# Sheet1.net
KiCad netlist of a schematic drawn in Altium Designer
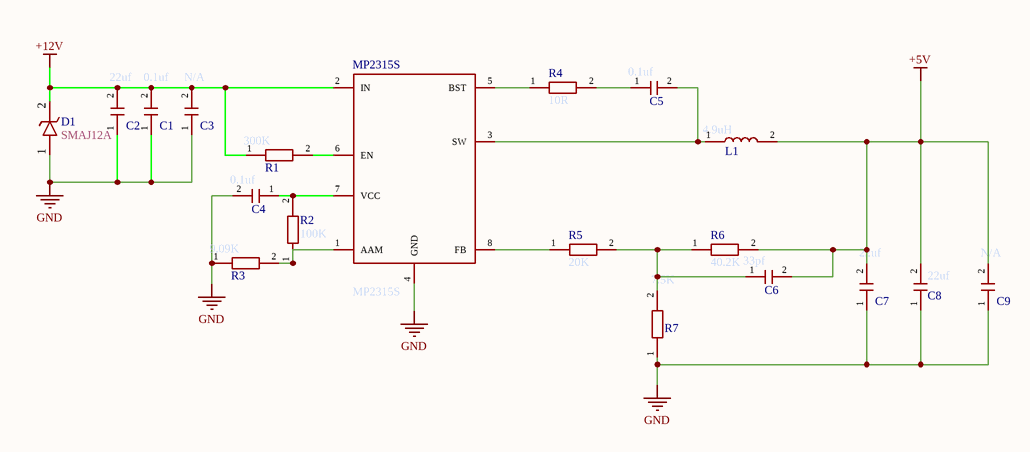
[diagram p0: Sheet1.SchDoc]

(export (version "E")
  (design (tool "Eeschema 10.0.6"))
  (components
    (comp (ref "C1") (value "0.1uf") (footprint "0603C") (libsource (lib "Schlib1") (part "capacitor")))
    (comp (ref "C2") (value "22uf") (footprint "1206C") (libsource (lib "Schlib1") (part "capacitor")))
    (comp (ref "C3") (value "N/A") (footprint "1206C") (libsource (lib "Schlib1") (part "capacitor")))
    (comp (ref "C4")
      (value "0.1uf")
      (footprint "www.zbpcb.com-JL_PCB:0603C")
      (libsource (lib "Schlib1") (part "capacitor"))
    )
    (comp (ref "C5")
      (value "0.1uf")
      (footprint "www.zbpcb.com-JL_PCB:0603C")
      (libsource (lib "Schlib1") (part "capacitor"))
    )
    (comp (ref "C6") (value "33pf") (footprint "0603C") (libsource (lib "Schlib1") (part "capacitor")))
    (comp (ref "C7") (value "22uf") (footprint "0805c") (libsource (lib "Schlib1") (part "capacitor")))
    (comp (ref "C8") (value "22uf") (footprint "0805c") (libsource (lib "Schlib1") (part "capacitor")))
    (comp (ref "C9") (value "N/A") (footprint "0805c") (libsource (lib "Schlib1") (part "capacitor")))
    (comp (ref "D1") (value "SMAJ12A") (footprint "SMA") (libsource (lib "Schlib1") (part "D")))
    (comp (ref "L1") (value "4.9uH") (footprint "L_pcb") (libsource (lib "Schlib1") (part "inductance")))
    (comp (ref "MP2315S")
      (value "MP2315S")
      (footprint "MP2315_PCB")
      (libsource (lib "Schlib1") (part "MP2315S"))
    )
    (comp (ref "R1") (value "300K") (footprint "0603R") (libsource (lib "Schlib1") (part "resistance")))
    (comp (ref "R2") (value "100K") (footprint "0603R") (libsource (lib "Schlib1") (part "resistance")))
    (comp (ref "R3") (value "9.09K") (footprint "0603R") (libsource (lib "Schlib1") (part "resistance")))
    (comp (ref "R4") (value "10R") (footprint "0603R") (libsource (lib "Schlib1") (part "resistance")))
    (comp (ref "R5") (value "20K") (footprint "0603R") (libsource (lib "Schlib1") (part "resistance")))
    (comp (ref "R6") (value "40.2K") (footprint "0603R") (libsource (lib "Schlib1") (part "resistance")))
    (comp (ref "R7") (value "7.5K") (footprint "0603R") (libsource (lib "Schlib1") (part "resistance")))
  )
  (nets
    (net (code "1") (name "+5V") (class "Default")
      (node (ref "C6") (pin "2") (pinfunction "2_2") (pintype "passive"))
      (node (ref "C7") (pin "2") (pinfunction "2_2") (pintype "passive"))
      (node (ref "C8") (pin "2") (pinfunction "2_2") (pintype "passive"))
      (node (ref "C9") (pin "2") (pinfunction "2_2") (pintype "passive"))
      (node (ref "L1") (pin "2") (pinfunction "2_2") (pintype "passive"))
      (node (ref "R6") (pin "2") (pinfunction "2_2") (pintype "passive"))
    )
    (net (code "2") (name "+12V") (class "Default")
      (node (ref "C1") (pin "2") (pinfunction "2_2") (pintype "passive"))
      (node (ref "C2") (pin "2") (pinfunction "2_2") (pintype "passive"))
      (node (ref "C3") (pin "2") (pinfunction "2_2") (pintype "passive"))
      (node (ref "D1") (pin "2") (pinfunction "2_2") (pintype "passive"))
      (node (ref "MP2315S") (pin "2") (pinfunction "IN_2") (pintype "passive"))
      (node (ref "R1") (pin "1") (pinfunction "1_1") (pintype "passive"))
    )
    (net (code "3") (name "GND") (class "Default")
      (node (ref "C1") (pin "1") (pinfunction "1_1") (pintype "passive"))
      (node (ref "C2") (pin "1") (pinfunction "1_1") (pintype "passive"))
      (node (ref "C3") (pin "1") (pinfunction "1_1") (pintype "passive"))
      (node (ref "C4") (pin "2") (pinfunction "2_2") (pintype "passive"))
      (node (ref "C7") (pin "1") (pinfunction "1_1") (pintype "passive"))
      (node (ref "C8") (pin "1") (pinfunction "1_1") (pintype "passive"))
      (node (ref "C9") (pin "1") (pinfunction "1_1") (pintype "passive"))
      (node (ref "D1") (pin "1") (pinfunction "1_1") (pintype "passive"))
      (node (ref "MP2315S") (pin "4") (pinfunction "GND_4") (pintype "passive"))
      (node (ref "R3") (pin "1") (pinfunction "1_1") (pintype "passive"))
      (node (ref "R7") (pin "1") (pinfunction "1_1") (pintype "passive"))
    )
    (net (code "4") (name "Net-(C5-Pad1)") (class "Default")
      (node (ref "C5") (pin "1") (pinfunction "1_1") (pintype "passive"))
      (node (ref "R4") (pin "2") (pinfunction "2_2") (pintype "passive"))
    )
    (net (code "5") (name "Net-(C6-Pad1)") (class "Default")
      (node (ref "C6") (pin "1") (pinfunction "1_1") (pintype "passive"))
      (node (ref "R5") (pin "2") (pinfunction "2_2") (pintype "passive"))
      (node (ref "R6") (pin "1") (pinfunction "1_1") (pintype "passive"))
      (node (ref "R7") (pin "2") (pinfunction "2_2") (pintype "passive"))
    )
    (net (code "6") (name "Net-(MP2315S-AAM)") (class "Default")
      (node (ref "MP2315S") (pin "1") (pinfunction "AAM_1") (pintype "passive"))
      (node (ref "R2") (pin "1") (pinfunction "1_1") (pintype "passive"))
      (node (ref "R3") (pin "2") (pinfunction "2_2") (pintype "passive"))
    )
    (net (code "7") (name "Net-(MP2315S-BST)") (class "Default")
      (node (ref "MP2315S") (pin "5") (pinfunction "BST_5") (pintype "passive"))
      (node (ref "R4") (pin "1") (pinfunction "1_1") (pintype "passive"))
    )
    (net (code "8") (name "Net-(MP2315S-EN)") (class "Default")
      (node (ref "MP2315S") (pin "6") (pinfunction "EN_6") (pintype "passive"))
      (node (ref "R1") (pin "2") (pinfunction "2_2") (pintype "passive"))
    )
    (net (code "9") (name "Net-(MP2315S-FB)") (class "Default")
      (node (ref "MP2315S") (pin "8") (pinfunction "FB_8") (pintype "passive"))
      (node (ref "R5") (pin "1") (pinfunction "1_1") (pintype "passive"))
    )
    (net (code "10") (name "Net-(MP2315S-SW)") (class "Default")
      (node (ref "C5") (pin "2") (pinfunction "2_2") (pintype "passive"))
      (node (ref "L1") (pin "1") (pinfunction "1_1") (pintype "passive"))
      (node (ref "MP2315S") (pin "3") (pinfunction "SW_3") (pintype "passive"))
    )
    (net (code "11") (name "Net-(MP2315S-VCC)") (class "Default")
      (node (ref "C4") (pin "1") (pinfunction "1_1") (pintype "passive"))
      (node (ref "MP2315S") (pin "7") (pinfunction "VCC_7") (pintype "passive"))
      (node (ref "R2") (pin "2") (pinfunction "2_2") (pintype "passive"))
    )
  )
)
